# contactor_connectors.net
KiCad netlist of a schematic drawn in Altium Designer
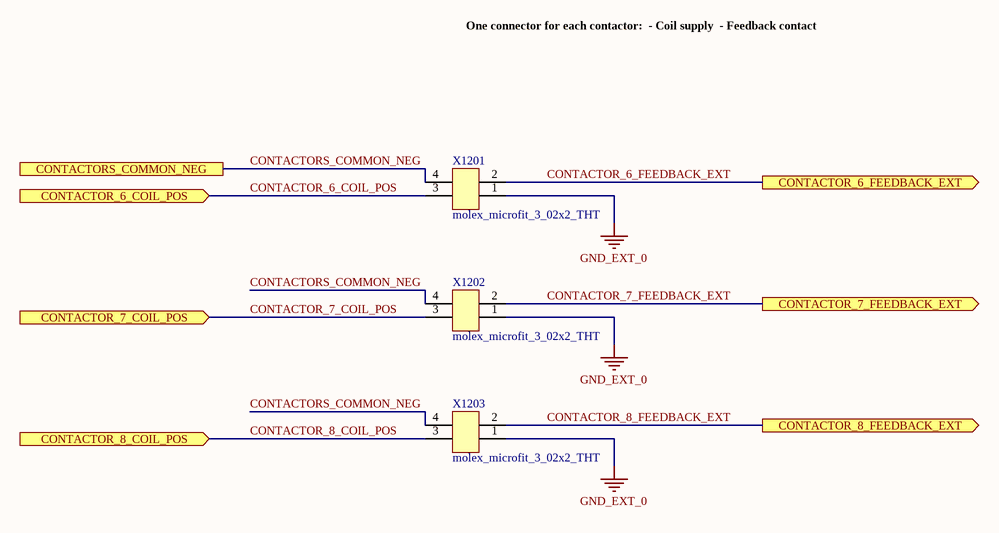
[diagram p0: contactor_connectors.SchDoc]

(export (version "E")
  (design (tool "Eeschema 10.0.6"))
  (components
    (comp (ref "X1201")
      (value "molex_microfit_3_02x2_THT")
      (footprint "43045-0421")
      (fields (field (name "MANUFACTURER") "Molex"))
      (libsource (lib "OE750") (part "X2x2"))
    )
    (comp (ref "X1202")
      (value "molex_microfit_3_02x2_THT")
      (footprint "43045-0421")
      (fields (field (name "MANUFACTURER") "Molex"))
      (libsource (lib "OE750") (part "X2x2"))
    )
    (comp (ref "X1203")
      (value "molex_microfit_3_02x2_THT")
      (footprint "43045-0421")
      (fields (field (name "MANUFACTURER") "Molex"))
      (libsource (lib "OE750") (part "X2x2"))
    )
  )
  (nets
    (net (code "1") (name "/CONTACTORS_COMMON_NEG") (class "Default")
      (node (ref "X1201") (pin "4") (pintype "passive"))
      (node (ref "X1202") (pin "4") (pintype "passive"))
      (node (ref "X1203") (pin "4") (pintype "passive"))
    )
    (net (code "2") (name "/CONTACTOR_6_COIL_POS") (class "Default")
      (node (ref "X1201") (pin "3") (pintype "passive"))
    )
    (net (code "3") (name "/CONTACTOR_6_FEEDBACK_EXT") (class "Default")
      (node (ref "X1201") (pin "2") (pintype "passive"))
    )
    (net (code "4") (name "/CONTACTOR_7_COIL_POS") (class "Default")
      (node (ref "X1202") (pin "3") (pintype "passive"))
    )
    (net (code "5") (name "/CONTACTOR_7_FEEDBACK_EXT") (class "Default")
      (node (ref "X1202") (pin "2") (pintype "passive"))
    )
    (net (code "6") (name "/CONTACTOR_8_COIL_POS") (class "Default")
      (node (ref "X1203") (pin "3") (pintype "passive"))
    )
    (net (code "7") (name "/CONTACTOR_8_FEEDBACK_EXT") (class "Default")
      (node (ref "X1203") (pin "2") (pintype "passive"))
    )
    (net (code "8") (name "GND_EXT_0") (class "Default")
      (node (ref "X1201") (pin "1") (pintype "passive"))
      (node (ref "X1202") (pin "1") (pintype "passive"))
      (node (ref "X1203") (pin "1") (pintype "passive"))
    )
  )
)
